# AjusteVoltajeTX.net
KiCad netlist of a schematic drawn in Altium Designer
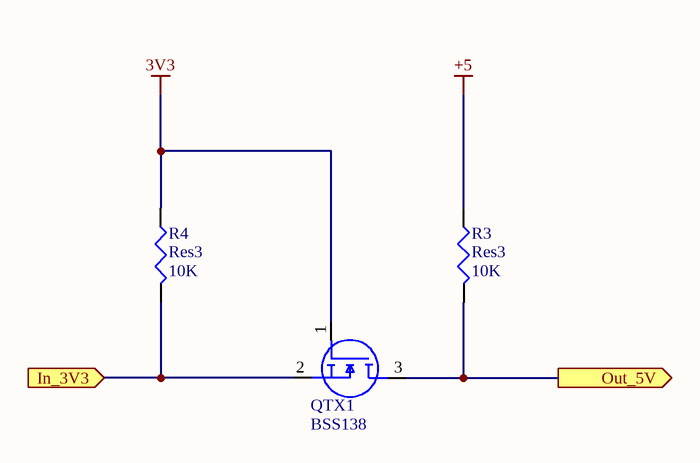
[diagram p0: AjusteVoltajeTX.SchDoc]

(export (version "E")
  (design (tool "Eeschema 10.0.6"))
  (components
    (comp (ref "QTX1")
      (value "BSS138")
      (footprint "ComponentesLayOut:SOT95P240X120-3N")
      (description "MOSFET (N-Channel)")
      (fields (field (name "MOUSER PART NUMBER") "512-BSS138"))
      (libsource (lib "CompontentesEsquemáticos") (part "BSS138"))
    )
    (comp (ref "R3")
      (value "Res3")
      (footprint "J1-0603")
      (description "Resistor")
      (fields (field (name "ALTIUM_VALUE") "10K") (field (name "PUBLISHER") "Altium Limited"))
      (libsource (lib "Miscellaneous Devices") (part "Res3"))
    )
    (comp (ref "R4")
      (value "Res3")
      (footprint "J1-0603")
      (description "Resistor")
      (fields (field (name "ALTIUM_VALUE") "10K") (field (name "PUBLISHER") "Altium Limited"))
      (libsource (lib "Miscellaneous Devices") (part "Res3"))
    )
  )
  (nets
    (net (code "1") (name "+5") (class "Default")
      (node (ref "R3") (pin "1") (pinfunction "1_1") (pintype "passive"))
    )
    (net (code "2") (name "/In_3V3") (class "Default")
      (node (ref "QTX1") (pin "2") (pinfunction "S_2") (pintype "passive"))
      (node (ref "R4") (pin "2") (pinfunction "2_2") (pintype "passive"))
    )
    (net (code "3") (name "/Out_5V") (class "Default")
      (node (ref "QTX1") (pin "3") (pinfunction "D_3") (pintype "passive"))
      (node (ref "R3") (pin "2") (pinfunction "2_2") (pintype "passive"))
    )
    (net (code "4") (name "3V3") (class "Default")
      (node (ref "QTX1") (pin "1") (pinfunction "G_1") (pintype "passive"))
      (node (ref "R4") (pin "1") (pinfunction "1_1") (pintype "passive"))
    )
  )
)
